# tic12400.net
KiCad netlist of a schematic drawn in EAGLE
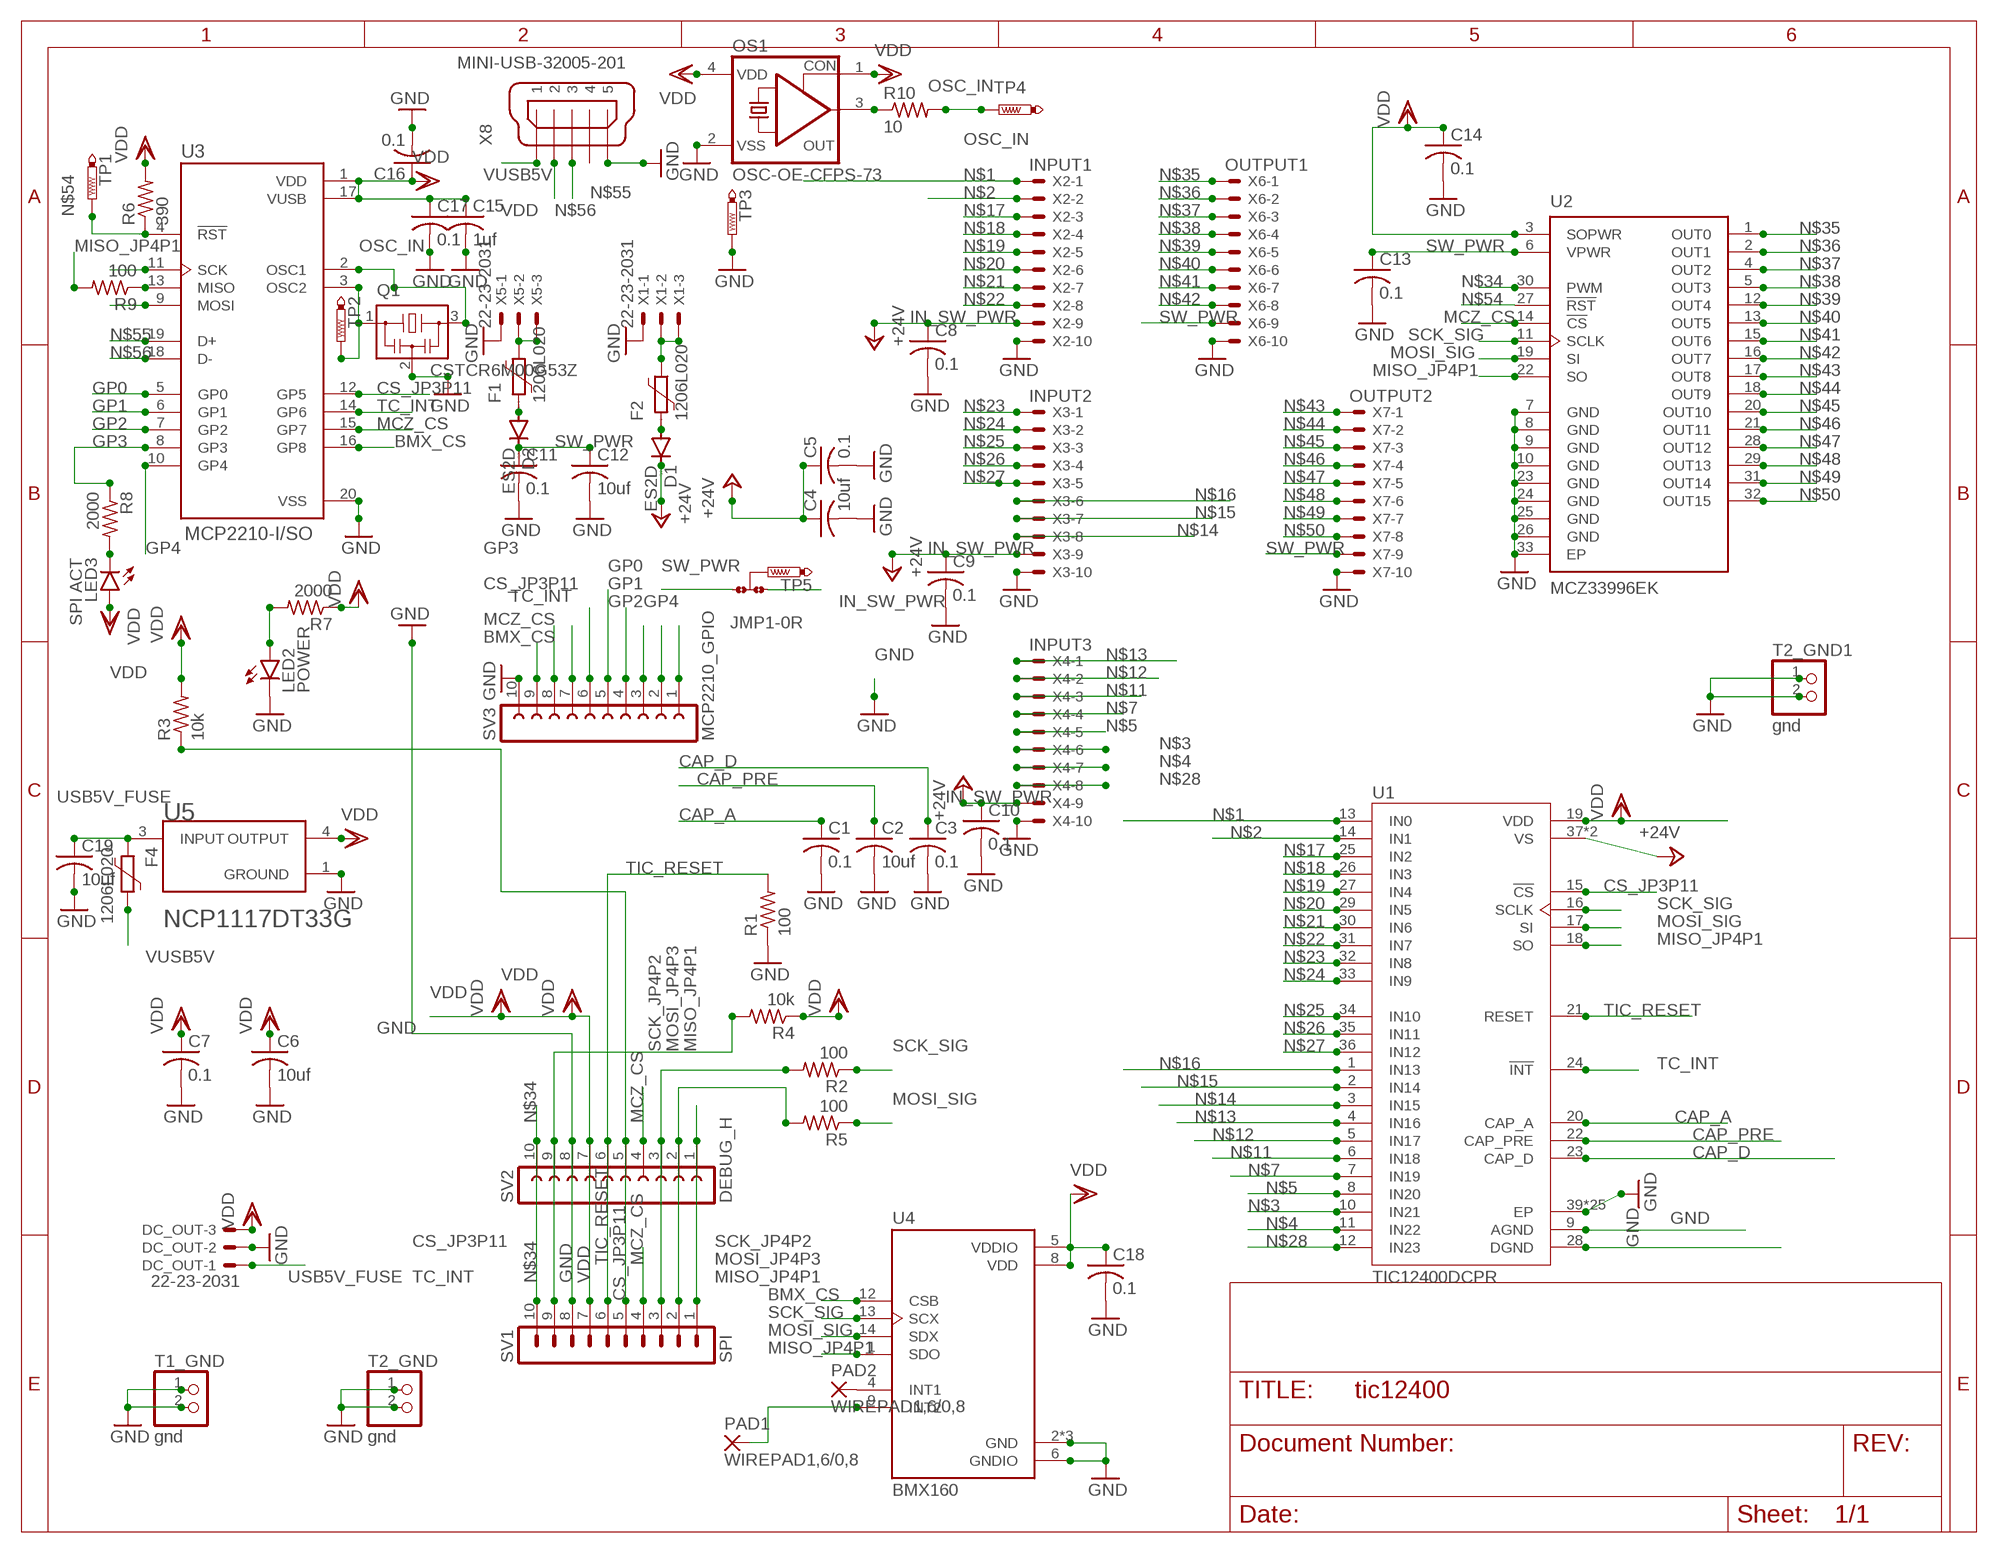
[diagram p0: schematic, sheet 1]

(export (version "E")
  (design (tool "Eeschema 10.0.6"))
  (components
    (comp (ref "C1")
      (value "0.1")
      (footprint "eagle-import:C0805")
      (libsource (lib "eagle-import") (part "C-USC0805"))
    )
    (comp (ref "C2")
      (value "10uf")
      (footprint "eagle-import:C0805")
      (libsource (lib "eagle-import") (part "C-USC0805"))
    )
    (comp (ref "C3")
      (value "0.1")
      (footprint "eagle-import:C0805")
      (libsource (lib "eagle-import") (part "C-USC0805"))
    )
    (comp (ref "C4")
      (value "10uf")
      (footprint "eagle-import:C0805")
      (libsource (lib "eagle-import") (part "C-USC0805"))
    )
    (comp (ref "C5")
      (value "0.1")
      (footprint "eagle-import:C0805")
      (libsource (lib "eagle-import") (part "C-USC0805"))
    )
    (comp (ref "C6")
      (value "10uf")
      (footprint "eagle-import:C0805")
      (libsource (lib "eagle-import") (part "C-USC0805"))
    )
    (comp (ref "C7")
      (value "0.1")
      (footprint "eagle-import:C0805")
      (libsource (lib "eagle-import") (part "C-USC0805"))
    )
    (comp (ref "C8")
      (value "0.1")
      (footprint "eagle-import:C0805")
      (libsource (lib "eagle-import") (part "C-USC0805"))
    )
    (comp (ref "C9")
      (value "0.1")
      (footprint "eagle-import:C0805")
      (libsource (lib "eagle-import") (part "C-USC0805"))
    )
    (comp (ref "C10")
      (value "0.1")
      (footprint "eagle-import:C0805")
      (libsource (lib "eagle-import") (part "C-USC0805"))
    )
    (comp (ref "C11")
      (value "0.1")
      (footprint "eagle-import:C0805")
      (libsource (lib "eagle-import") (part "C-USC0805"))
    )
    (comp (ref "C12")
      (value "10uf")
      (footprint "eagle-import:C0805")
      (libsource (lib "eagle-import") (part "C-USC0805"))
    )
    (comp (ref "C13")
      (value "0.1")
      (footprint "eagle-import:C0805")
      (libsource (lib "eagle-import") (part "C-USC0805"))
    )
    (comp (ref "C14")
      (value "0.1")
      (footprint "eagle-import:C0805")
      (libsource (lib "eagle-import") (part "C-USC0805"))
    )
    (comp (ref "C15")
      (value "1uf")
      (footprint "eagle-import:C0805")
      (libsource (lib "eagle-import") (part "C-USC0805"))
    )
    (comp (ref "C16")
      (value "0.1")
      (footprint "eagle-import:C0805")
      (libsource (lib "eagle-import") (part "C-USC0805"))
    )
    (comp (ref "C17")
      (value "0.1")
      (footprint "eagle-import:C0805")
      (libsource (lib "eagle-import") (part "C-USC0805"))
    )
    (comp (ref "C18")
      (value "0.1")
      (footprint "eagle-import:C0805")
      (libsource (lib "eagle-import") (part "C-USC0805"))
    )
    (comp (ref "C19")
      (value "10uf")
      (footprint "eagle-import:C0805")
      (libsource (lib "eagle-import") (part "C-USC0805"))
    )
    (comp (ref "D1")
      (value "ES2D")
      (footprint "eagle-import:SMB")
      (libsource (lib "eagle-import") (part "ES2D"))
    )
    (comp (ref "D2")
      (value "ES2D")
      (footprint "eagle-import:SMB")
      (libsource (lib "eagle-import") (part "ES2D"))
    )
    (comp (ref "DC_OUT")
      (value "22-23-2031")
      (footprint "eagle-import:22-23-2031")
      (fields (field (name "MF") "MOLEX"))
      (libsource (lib "eagle-import") (part "22-23-2031"))
    )
    (comp (ref "F1")
      (value "1206L020")
      (footprint "eagle-import:1206L")
      (fields (field (name "MF") "Littelfuse"))
      (libsource (lib "eagle-import") (part "?1206L020"))
    )
    (comp (ref "F2")
      (value "1206L020")
      (footprint "eagle-import:1206L")
      (fields (field (name "MF") "Littelfuse"))
      (libsource (lib "eagle-import") (part "?1206L020"))
    )
    (comp (ref "F4")
      (value "1206L020")
      (footprint "eagle-import:1206L")
      (fields (field (name "MF") "Littelfuse"))
      (libsource (lib "eagle-import") (part "?1206L020"))
    )
    (comp (ref "JMP1")
      (value "+24_CONNECT")
      (footprint "eagle-import:A0R-JMP")
      (libsource (lib "eagle-import") (part "0R-JUMPA"))
    )
    (comp (ref "LED2")
      (value "POWER")
      (footprint "eagle-import:CHIP-LED0805")
      (libsource (lib "eagle-import") (part "LEDCHIP-LED0805"))
    )
    (comp (ref "LED3")
      (value "SPI ACT")
      (footprint "eagle-import:CHIP-LED0805")
      (libsource (lib "eagle-import") (part "LEDCHIP-LED0805"))
    )
    (comp (ref "OS1")
      (value "OSC-OE-CFPS-73")
      (footprint "eagle-import:7.2X5.2-4-PAD")
      (libsource (lib "eagle-import") (part "OSC-OE-CFPS-73"))
    )
    (comp (ref "PAD1")
      (value "WIREPAD1,6/0,8")
      (footprint "eagle-import:1,6_0,8")
      (libsource (lib "eagle-import") (part "WIREPAD1,6/0,8"))
    )
    (comp (ref "PAD2")
      (value "WIREPAD1,6/0,8")
      (footprint "eagle-import:1,6_0,8")
      (libsource (lib "eagle-import") (part "WIREPAD1,6/0,8"))
    )
    (comp (ref "Q1")
      (value "CSTCR6M00G53Z")
      (footprint "eagle-import:CSTCR6M")
      (fields (field (name "MPN") "CSTCR6M00G53-R0"))
      (libsource (lib "eagle-import") (part "CSTCR6M00G53Z"))
    )
    (comp (ref "R1")
      (value "100")
      (footprint "eagle-import:R0805")
      (libsource (lib "eagle-import") (part "R-US_R0805"))
    )
    (comp (ref "R2")
      (value "100")
      (footprint "eagle-import:R0805")
      (libsource (lib "eagle-import") (part "R-US_R0805"))
    )
    (comp (ref "R3")
      (value "10k")
      (footprint "eagle-import:R0805")
      (libsource (lib "eagle-import") (part "R-US_R0805"))
    )
    (comp (ref "R4")
      (value "10k")
      (footprint "eagle-import:R0805")
      (libsource (lib "eagle-import") (part "R-US_R0805"))
    )
    (comp (ref "R5")
      (value "100")
      (footprint "eagle-import:R0805")
      (libsource (lib "eagle-import") (part "R-US_R0805"))
    )
    (comp (ref "R6")
      (value "390")
      (footprint "eagle-import:R0805")
      (libsource (lib "eagle-import") (part "R-US_R0805"))
    )
    (comp (ref "R7")
      (value "2000")
      (footprint "eagle-import:R0805")
      (libsource (lib "eagle-import") (part "R-US_R0805"))
    )
    (comp (ref "R8")
      (value "2000")
      (footprint "eagle-import:R0805")
      (libsource (lib "eagle-import") (part "R-US_R0805"))
    )
    (comp (ref "R9")
      (value "100")
      (footprint "eagle-import:R0805")
      (libsource (lib "eagle-import") (part "R-US_R0805"))
    )
    (comp (ref "R10")
      (value "10")
      (footprint "eagle-import:R0805")
      (libsource (lib "eagle-import") (part "R-US_R0805"))
    )
    (comp (ref "SV1")
      (value "SPI")
      (footprint "eagle-import:MA10-1")
      (libsource (lib "eagle-import") (part "MA10-1"))
    )
    (comp (ref "SV2")
      (value "DEBUG_H")
      (footprint "eagle-import:FE10")
      (libsource (lib "eagle-import") (part "FE10-1"))
    )
    (comp (ref "SV3")
      (value "MCP2210_GPIO")
      (footprint "eagle-import:FE10")
      (libsource (lib "eagle-import") (part "FE10-1"))
    )
    (comp (ref "T1_GND")
      (value "gnd")
      (footprint "eagle-import:1X02")
      (libsource (lib "eagle-import") (part "PINHD-1X2"))
    )
    (comp (ref "T2_GND")
      (value "gnd")
      (footprint "eagle-import:1X02")
      (libsource (lib "eagle-import") (part "PINHD-1X2"))
    )
    (comp (ref "T2_GND1")
      (value "gnd")
      (footprint "eagle-import:1X02")
      (libsource (lib "eagle-import") (part "PINHD-1X2"))
    )
    (comp (ref "TP1")
      (value "PTR1B1,27")
      (footprint "eagle-import:B1,27")
      (libsource (lib "eagle-import") (part "PTR1B1,27"))
    )
    (comp (ref "TP2")
      (value "PTR1B1,27")
      (footprint "eagle-import:B1,27")
      (libsource (lib "eagle-import") (part "PTR1B1,27"))
    )
    (comp (ref "TP3")
      (value "PTR1B1,27")
      (footprint "eagle-import:B1,27")
      (libsource (lib "eagle-import") (part "PTR1B1,27"))
    )
    (comp (ref "TP4")
      (value "PTR1B1,27")
      (footprint "eagle-import:B1,27")
      (libsource (lib "eagle-import") (part "PTR1B1,27"))
    )
    (comp (ref "TP5")
      (value "PTR1B1,27")
      (footprint "eagle-import:B1,27")
      (libsource (lib "eagle-import") (part "PTR1B1,27"))
    )
    (comp (ref "U1")
      (value "TIC12400DCPR")
      (footprint "eagle-import:SOP50P640X120-38N")
      (fields (field (name "DIGI-KEY_PART_NUMBER") "296-47492-1-ND") (field (name "MF") "Texas Instruments"))
      (libsource (lib "eagle-import") (part "TIC12400DCPR"))
    )
    (comp (ref "U2")
      (value "MCZ33996EK")
      (footprint "eagle-import:SOP65P1030X265-33N")
      (fields (field (name "MF") "NXP USA"))
      (libsource (lib "eagle-import") (part "MCZ33996EK"))
    )
    (comp (ref "U3")
      (value "MCP2210-I/SO")
      (footprint "eagle-import:SOP65P780X200-20N")
      (fields (field (name "MF") "Microchip Technology"))
      (libsource (lib "eagle-import") (part "MCP2210-I/SO"))
    )
    (comp (ref "U4")
      (value "BMX160")
      (footprint "eagle-import:PQFN50P250X300X100-14N")
      (fields (field (name "MF") "Bosch Sensortec"))
      (libsource (lib "eagle-import") (part "BMX160"))
    )
    (comp (ref "U5")
      (value "ON_SEMICONDUCTOR_NCP1117DT33GON_SEMICONDUCTOR_NCP1117DT33G_0_0")
      (footprint "eagle-import:ON_SEMICONDUCTOR_NCP1117DT33G_0")
      (fields
        (field (name "DIGIKEY_PART_NUMBER") "NCP1117DT33GOS-ND")
        (field (name "MF") "ON Semiconductor")
        (field (name "MOUSER_PART_NUMBER") "863-NCP1117DT33G")
      )
      (libsource (lib "eagle-import") (part "ON_SEMICONDUCTOR_NCP1117DT33GON_SEMICONDUCTOR_NCP1117DT33G_0_0"))
    )
    (comp (ref "X1")
      (value "22-23-2031")
      (footprint "eagle-import:22-23-2031")
      (fields (field (name "MF") "MOLEX"))
      (libsource (lib "eagle-import") (part "22-23-2031"))
    )
    (comp (ref "X2")
      (value "INPUT1")
      (footprint "eagle-import:KK-156-10")
      (fields (field (name "MF") "MOLEX"))
      (libsource (lib "eagle-import") (part "KK-156-10"))
    )
    (comp (ref "X3")
      (value "INPUT2")
      (footprint "eagle-import:KK-156-10")
      (fields (field (name "MF") "MOLEX"))
      (libsource (lib "eagle-import") (part "KK-156-10"))
    )
    (comp (ref "X4")
      (value "INPUT3")
      (footprint "eagle-import:KK-156-10")
      (fields (field (name "MF") "MOLEX"))
      (libsource (lib "eagle-import") (part "KK-156-10"))
    )
    (comp (ref "X5")
      (value "22-23-2031")
      (footprint "eagle-import:22-23-2031")
      (fields (field (name "MF") "MOLEX"))
      (libsource (lib "eagle-import") (part "22-23-2031"))
    )
    (comp (ref "X6")
      (value "OUTPUT1")
      (footprint "eagle-import:KK-156-10")
      (fields (field (name "MF") "MOLEX"))
      (libsource (lib "eagle-import") (part "KK-156-10"))
    )
    (comp (ref "X7")
      (value "OUTPUT2")
      (footprint "eagle-import:KK-156-10")
      (fields (field (name "MF") "MOLEX"))
      (libsource (lib "eagle-import") (part "KK-156-10"))
    )
    (comp (ref "X8")
      (value "MINI-USB-32005-201")
      (footprint "eagle-import:32005-201")
      (libsource (lib "eagle-import") (part "MINI-USB-32005-201"))
    )
  )
  (nets
    (net (code "1") (name "+24V") (class "Default")
      (node (ref "C10") (pin "1") (pinfunction "1_1") (pintype "passive"))
      (node (ref "C4") (pin "1") (pinfunction "1_1") (pintype "passive"))
      (node (ref "C5") (pin "1") (pinfunction "1_1") (pintype "passive"))
      (node (ref "C8") (pin "1") (pinfunction "1_1") (pintype "passive"))
      (node (ref "C9") (pin "1") (pinfunction "1_1") (pintype "passive"))
      (node (ref "D1") (pin "C") (pinfunction "C_C") (pintype "passive"))
      (node (ref "JMP1") (pin "3") (pinfunction "3_3") (pintype "passive"))
      (node (ref "U1") (pin "37") (pinfunction "VS_37") (pintype "power_in"))
      (node (ref "U1") (pin "38") (pinfunction "VS_38") (pintype "power_in"))
      (node (ref "X2") (pin "9") (pinfunction "S_9") (pintype "passive"))
      (node (ref "X3") (pin "9") (pinfunction "S_9") (pintype "passive"))
      (node (ref "X4") (pin "9") (pinfunction "S_9") (pintype "passive"))
    )
    (net (code "2") (name "/BMX_CS") (class "Default")
      (node (ref "SV3") (pin "9") (pinfunction "9_9") (pintype "passive"))
      (node (ref "U3") (pin "16") (pinfunction "GP8_16") (pintype "bidirectional"))
      (node (ref "U4") (pin "12") (pinfunction "CSB_12") (pintype "input"))
    )
    (net (code "3") (name "/CAP_A") (class "Default")
      (node (ref "C1") (pin "1") (pinfunction "1_1") (pintype "passive"))
      (node (ref "U1") (pin "20") (pinfunction "CAP_A_20") (pintype "passive"))
    )
    (net (code "4") (name "/CAP_D") (class "Default")
      (node (ref "C3") (pin "1") (pinfunction "1_1") (pintype "passive"))
      (node (ref "U1") (pin "23") (pinfunction "CAP_D_23") (pintype "passive"))
    )
    (net (code "5") (name "/CAP_PRE") (class "Default")
      (node (ref "C2") (pin "1") (pinfunction "1_1") (pintype "passive"))
      (node (ref "U1") (pin "22") (pinfunction "CAP_PRE_22") (pintype "passive"))
    )
    (net (code "6") (name "/CS_JP3P11") (class "Default")
      (node (ref "R3") (pin "1") (pinfunction "1_1") (pintype "passive"))
      (node (ref "SV1") (pin "5") (pinfunction "5_5") (pintype "passive"))
      (node (ref "SV2") (pin "5") (pinfunction "5_5") (pintype "passive"))
      (node (ref "SV3") (pin "6") (pinfunction "6_6") (pintype "passive"))
      (node (ref "U1") (pin "15") (pinfunction "~{CS}_15") (pintype "input"))
      (node (ref "U3") (pin "12") (pinfunction "GP5_12") (pintype "bidirectional"))
    )
    (net (code "7") (name "/GP0") (class "Default")
      (node (ref "SV3") (pin "1") (pinfunction "1_1") (pintype "passive"))
      (node (ref "U3") (pin "5") (pinfunction "GP0_5") (pintype "bidirectional"))
    )
    (net (code "8") (name "/GP1") (class "Default")
      (node (ref "SV3") (pin "2") (pinfunction "2_2") (pintype "passive"))
      (node (ref "U3") (pin "6") (pinfunction "GP1_6") (pintype "bidirectional"))
    )
    (net (code "9") (name "/GP2") (class "Default")
      (node (ref "SV3") (pin "3") (pinfunction "3_3") (pintype "passive"))
      (node (ref "U3") (pin "7") (pinfunction "GP2_7") (pintype "bidirectional"))
    )
    (net (code "10") (name "/GP3") (class "Default")
      (node (ref "R8") (pin "1") (pinfunction "1_1") (pintype "passive"))
      (node (ref "SV3") (pin "4") (pinfunction "4_4") (pintype "passive"))
      (node (ref "U3") (pin "8") (pinfunction "GP3_8") (pintype "bidirectional"))
    )
    (net (code "11") (name "/GP4") (class "Default")
      (node (ref "SV3") (pin "5") (pinfunction "5_5") (pintype "passive"))
      (node (ref "U3") (pin "10") (pinfunction "GP4_10") (pintype "bidirectional"))
    )
    (net (code "12") (name "/MCZ_CS") (class "Default")
      (node (ref "SV1") (pin "4") (pinfunction "4_4") (pintype "passive"))
      (node (ref "SV2") (pin "4") (pinfunction "4_4") (pintype "passive"))
      (node (ref "SV3") (pin "8") (pinfunction "8_8") (pintype "passive"))
      (node (ref "U2") (pin "14") (pinfunction "~{CS}_14") (pintype "input"))
      (node (ref "U3") (pin "15") (pinfunction "GP7_15") (pintype "bidirectional"))
    )
    (net (code "13") (name "/MISO_JP4P1") (class "Default")
      (node (ref "R9") (pin "2") (pinfunction "2_2") (pintype "passive"))
      (node (ref "SV1") (pin "1") (pinfunction "1_1") (pintype "passive"))
      (node (ref "SV2") (pin "1") (pinfunction "1_1") (pintype "passive"))
      (node (ref "U1") (pin "18") (pinfunction "SO_18") (pintype "output"))
      (node (ref "U2") (pin "22") (pinfunction "SO_22") (pintype "output"))
      (node (ref "U4") (pin "1") (pinfunction "SDO_1") (pintype "bidirectional"))
    )
    (net (code "14") (name "/MOSI_JP4P3") (class "Default")
      (node (ref "R5") (pin "2") (pinfunction "2_2") (pintype "passive"))
      (node (ref "SV1") (pin "2") (pinfunction "2_2") (pintype "passive"))
      (node (ref "SV2") (pin "2") (pinfunction "2_2") (pintype "passive"))
    )
    (net (code "15") (name "/MOSI_SIG") (class "Default")
      (node (ref "R5") (pin "1") (pinfunction "1_1") (pintype "passive"))
      (node (ref "U1") (pin "17") (pinfunction "SI_17") (pintype "input"))
      (node (ref "U2") (pin "19") (pinfunction "SI_19") (pintype "input"))
      (node (ref "U3") (pin "9") (pinfunction "MOSI_9") (pintype "output"))
      (node (ref "U4") (pin "14") (pinfunction "SDX_14") (pintype "bidirectional"))
    )
    (net (code "16") (name "/N$1") (class "Default")
      (node (ref "U1") (pin "13") (pinfunction "IN0_13") (pintype "bidirectional"))
      (node (ref "X2") (pin "1") (pinfunction "S_1") (pintype "passive"))
    )
    (net (code "17") (name "/N$2") (class "Default")
      (node (ref "U1") (pin "14") (pinfunction "IN1_14") (pintype "bidirectional"))
      (node (ref "X2") (pin "2") (pinfunction "S_2") (pintype "passive"))
    )
    (net (code "18") (name "/N$3") (class "Default")
      (node (ref "U1") (pin "10") (pinfunction "IN21_10") (pintype "bidirectional"))
      (node (ref "X4") (pin "6") (pinfunction "S_6") (pintype "passive"))
    )
    (net (code "19") (name "/N$4") (class "Default")
      (node (ref "U1") (pin "11") (pinfunction "IN22_11") (pintype "bidirectional"))
      (node (ref "X4") (pin "7") (pinfunction "S_7") (pintype "passive"))
    )
    (net (code "20") (name "/N$5") (class "Default")
      (node (ref "U1") (pin "8") (pinfunction "IN20_8") (pintype "bidirectional"))
      (node (ref "X4") (pin "5") (pinfunction "S_5") (pintype "passive"))
    )
    (net (code "21") (name "/N$7") (class "Default")
      (node (ref "U1") (pin "7") (pinfunction "IN19_7") (pintype "bidirectional"))
      (node (ref "X4") (pin "4") (pinfunction "S_4") (pintype "passive"))
    )
    (net (code "22") (name "/N$11") (class "Default")
      (node (ref "U1") (pin "6") (pinfunction "IN18_6") (pintype "bidirectional"))
      (node (ref "X4") (pin "3") (pinfunction "S_3") (pintype "passive"))
    )
    (net (code "23") (name "/N$12") (class "Default")
      (node (ref "U1") (pin "5") (pinfunction "IN17_5") (pintype "bidirectional"))
      (node (ref "X4") (pin "2") (pinfunction "S_2") (pintype "passive"))
    )
    (net (code "24") (name "/N$13") (class "Default")
      (node (ref "U1") (pin "4") (pinfunction "IN16_4") (pintype "bidirectional"))
      (node (ref "X4") (pin "1") (pinfunction "S_1") (pintype "passive"))
    )
    (net (code "25") (name "/N$14") (class "Default")
      (node (ref "U1") (pin "3") (pinfunction "IN15_3") (pintype "bidirectional"))
      (node (ref "X3") (pin "8") (pinfunction "S_8") (pintype "passive"))
    )
    (net (code "26") (name "/N$15") (class "Default")
      (node (ref "U1") (pin "2") (pinfunction "IN14_2") (pintype "bidirectional"))
      (node (ref "X3") (pin "7") (pinfunction "S_7") (pintype "passive"))
    )
    (net (code "27") (name "/N$16") (class "Default")
      (node (ref "U1") (pin "1") (pinfunction "IN13_1") (pintype "bidirectional"))
      (node (ref "X3") (pin "6") (pinfunction "S_6") (pintype "passive"))
    )
    (net (code "28") (name "/N$17") (class "Default")
      (node (ref "U1") (pin "25") (pinfunction "IN2_25") (pintype "bidirectional"))
      (node (ref "X2") (pin "3") (pinfunction "S_3") (pintype "passive"))
    )
    (net (code "29") (name "/N$18") (class "Default")
      (node (ref "U1") (pin "26") (pinfunction "IN3_26") (pintype "bidirectional"))
      (node (ref "X2") (pin "4") (pinfunction "S_4") (pintype "passive"))
    )
    (net (code "30") (name "/N$19") (class "Default")
      (node (ref "U1") (pin "27") (pinfunction "IN4_27") (pintype "bidirectional"))
      (node (ref "X2") (pin "5") (pinfunction "S_5") (pintype "passive"))
    )
    (net (code "31") (name "/N$20") (class "Default")
      (node (ref "U1") (pin "29") (pinfunction "IN5_29") (pintype "bidirectional"))
      (node (ref "X2") (pin "6") (pinfunction "S_6") (pintype "passive"))
    )
    (net (code "32") (name "/N$21") (class "Default")
      (node (ref "U1") (pin "30") (pinfunction "IN6_30") (pintype "bidirectional"))
      (node (ref "X2") (pin "7") (pinfunction "S_7") (pintype "passive"))
    )
    (net (code "33") (name "/N$22") (class "Default")
      (node (ref "U1") (pin "31") (pinfunction "IN7_31") (pintype "bidirectional"))
      (node (ref "X2") (pin "8") (pinfunction "S_8") (pintype "passive"))
    )
    (net (code "34") (name "/N$23") (class "Default")
      (node (ref "U1") (pin "32") (pinfunction "IN8_32") (pintype "bidirectional"))
      (node (ref "X3") (pin "1") (pinfunction "S_1") (pintype "passive"))
    )
    (net (code "35") (name "/N$24") (class "Default")
      (node (ref "U1") (pin "33") (pinfunction "IN9_33") (pintype "bidirectional"))
      (node (ref "X3") (pin "2") (pinfunction "S_2") (pintype "passive"))
    )
    (net (code "36") (name "/N$25") (class "Default")
      (node (ref "U1") (pin "34") (pinfunction "IN10_34") (pintype "bidirectional"))
      (node (ref "X3") (pin "3") (pinfunction "S_3") (pintype "passive"))
    )
    (net (code "37") (name "/N$26") (class "Default")
      (node (ref "U1") (pin "35") (pinfunction "IN11_35") (pintype "bidirectional"))
      (node (ref "X3") (pin "4") (pinfunction "S_4") (pintype "passive"))
    )
    (net (code "38") (name "/N$27") (class "Default")
      (node (ref "U1") (pin "36") (pinfunction "IN12_36") (pintype "bidirectional"))
      (node (ref "X3") (pin "5") (pinfunction "S_5") (pintype "passive"))
    )
    (net (code "39") (name "/N$28") (class "Default")
      (node (ref "U1") (pin "12") (pinfunction "IN23_12") (pintype "bidirectional"))
      (node (ref "X4") (pin "8") (pinfunction "S_8") (pintype "passive"))
    )
    (net (code "40") (name "/N$34") (class "Default")
      (node (ref "SV1") (pin "10") (pinfunction "10_10") (pintype "passive"))
      (node (ref "SV2") (pin "10") (pinfunction "10_10") (pintype "passive"))
      (node (ref "U2") (pin "30") (pinfunction "PWM_30") (pintype "input"))
    )
    (net (code "41") (name "/N$35") (class "Default")
      (node (ref "U2") (pin "1") (pinfunction "OUT0_1") (pintype "output"))
      (node (ref "X6") (pin "1") (pinfunction "S_1") (pintype "passive"))
    )
    (net (code "42") (name "/N$36") (class "Default")
      (node (ref "U2") (pin "2") (pinfunction "OUT1_2") (pintype "output"))
      (node (ref "X6") (pin "2") (pinfunction "S_2") (pintype "passive"))
    )
    (net (code "43") (name "/N$37") (class "Default")
      (node (ref "U2") (pin "4") (pinfunction "OUT2_4") (pintype "output"))
      (node (ref "X6") (pin "3") (pinfunction "S_3") (pintype "passive"))
    )
    (net (code "44") (name "/N$38") (class "Default")
      (node (ref "U2") (pin "5") (pinfunction "OUT3_5") (pintype "output"))
      (node (ref "X6") (pin "4") (pinfunction "S_4") (pintype "passive"))
    )
    (net (code "45") (name "/N$39") (class "Default")
      (node (ref "U2") (pin "12") (pinfunction "OUT4_12") (pintype "output"))
      (node (ref "X6") (pin "5") (pinfunction "S_5") (pintype "passive"))
    )
    (net (code "46") (name "/N$40") (class "Default")
      (node (ref "U2") (pin "13") (pinfunction "OUT5_13") (pintype "output"))
      (node (ref "X6") (pin "6") (pinfunction "S_6") (pintype "passive"))
    )
    (net (code "47") (name "/N$41") (class "Default")
      (node (ref "U2") (pin "15") (pinfunction "OUT6_15") (pintype "output"))
      (node (ref "X6") (pin "7") (pinfunction "S_7") (pintype "passive"))
    )
    (net (code "48") (name "/N$42") (class "Default")
      (node (ref "U2") (pin "16") (pinfunction "OUT7_16") (pintype "output"))
      (node (ref "X6") (pin "8") (pinfunction "S_8") (pintype "passive"))
    )
    (net (code "49") (name "/N$43") (class "Default")
      (node (ref "U2") (pin "17") (pinfunction "OUT8_17") (pintype "output"))
      (node (ref "X7") (pin "1") (pinfunction "S_1") (pintype "passive"))
    )
    (net (code "50") (name "/N$44") (class "Default")
      (node (ref "U2") (pin "18") (pinfunction "OUT9_18") (pintype "output"))
      (node (ref "X7") (pin "2") (pinfunction "S_2") (pintype "passive"))
    )
    (net (code "51") (name "/N$45") (class "Default")
      (node (ref "U2") (pin "20") (pinfunction "OUT10_20") (pintype "output"))
      (node (ref "X7") (pin "3") (pinfunction "S_3") (pintype "passive"))
    )
    (net (code "52") (name "/N$46") (class "Default")
      (node (ref "U2") (pin "21") (pinfunction "OUT11_21") (pintype "output"))
      (node (ref "X7") (pin "4") (pinfunction "S_4") (pintype "passive"))
    )
    (net (code "53") (name "/N$47") (class "Default")
      (node (ref "U2") (pin "28") (pinfunction "OUT12_28") (pintype "output"))
      (node (ref "X7") (pin "5") (pinfunction "S_5") (pintype "passive"))
    )
    (net (code "54") (name "/N$48") (class "Default")
      (node (ref "U2") (pin "29") (pinfunction "OUT13_29") (pintype "output"))
      (node (ref "X7") (pin "6") (pinfunction "S_6") (pintype "passive"))
    )
    (net (code "55") (name "/N$49") (class "Default")
      (node (ref "U2") (pin "31") (pinfunction "OUT14_31") (pintype "output"))
      (node (ref "X7") (pin "7") (pinfunction "S_7") (pintype "passive"))
    )
    (net (code "56") (name "/N$50") (class "Default")
      (node (ref "U2") (pin "32") (pinfunction "OUT15_32") (pintype "output"))
      (node (ref "X7") (pin "8") (pinfunction "S_8") (pintype "passive"))
    )
    (net (code "57") (name "/N$54") (class "Default")
      (node (ref "R6") (pin "1") (pinfunction "1_1") (pintype "passive"))
      (node (ref "TP1") (pin "TP") (pinfunction "TP_TP") (pintype "input"))
      (node (ref "U2") (pin "27") (pinfunction "~{RST}_27") (pintype "input"))
      (node (ref "U3") (pin "4") (pinfunction "~{RST}_4") (pintype "input"))
    )
    (net (code "58") (name "/N$55") (class "Default")
      (node (ref "U3") (pin "19") (pinfunction "D+_19") (pintype "bidirectional"))
      (node (ref "X8") (pin "3") (pinfunction "3_3") (pintype "passive"))
    )
    (net (code "59") (name "/N$56") (class "Default")
      (node (ref "U3") (pin "18") (pinfunction "D-_18") (pintype "bidirectional"))
      (node (ref "X8") (pin "2") (pinfunction "2_2") (pintype "passive"))
    )
    (net (code "60") (name "/OSC_IN") (class "Default")
      (node (ref "Q1") (pin "3") (pinfunction "3_3") (pintype "passive"))
      (node (ref "R10") (pin "2") (pinfunction "2_2") (pintype "passive"))
      (node (ref "TP4") (pin "TP") (pinfunction "TP_TP") (pintype "input"))
      (node (ref "U3") (pin "2") (pinfunction "OSC1_2") (pintype "input"))
    )
    (net (code "61") (name "/SCK_JP4P2") (class "Default")
      (node (ref "R2") (pin "2") (pinfunction "2_2") (pintype "passive"))
      (node (ref "SV1") (pin "3") (pinfunction "3_3") (pintype "passive"))
      (node (ref "SV2") (pin "3") (pinfunction "3_3") (pintype "passive"))
    )
    (net (code "62") (name "/SCK_SIG") (class "Default")
      (node (ref "R2") (pin "1") (pinfunction "1_1") (pintype "passive"))
      (node (ref "U1") (pin "16") (pinfunction "SCLK_16") (pintype "input"))
      (node (ref "U2") (pin "11") (pinfunction "SCLK_11") (pintype "input"))
      (node (ref "U3") (pin "11") (pinfunction "SCK_11") (pintype "output"))
      (node (ref "U4") (pin "13") (pinfunction "SCX_13") (pintype "input"))
    )
    (net (code "63") (name "/SW_PWR") (class "Default")
      (node (ref "C11") (pin "1") (pinfunction "1_1") (pintype "passive"))
      (node (ref "C12") (pin "1") (pinfunction "1_1") (pintype "passive"))
      (node (ref "C13") (pin "1") (pinfunction "1_1") (pintype "passive"))
      (node (ref "D2") (pin "C") (pinfunction "C_C") (pintype "passive"))
      (node (ref "JMP1") (pin "1") (pinfunction "1_1") (pintype "passive"))
      (node (ref "U2") (pin "6") (pinfunction "VPWR_6") (pintype "power_in"))
      (node (ref "X6") (pin "9") (pinfunction "S_9") (pintype "passive"))
      (node (ref "X7") (pin "9") (pinfunction "S_9") (pintype "passive"))
    )
    (net (code "64") (name "/TC_INT") (class "Default")
      (node (ref "R4") (pin "2") (pinfunction "2_2") (pintype "passive"))
      (node (ref "SV1") (pin "9") (pinfunction "9_9") (pintype "passive"))
      (node (ref "SV2") (pin "9") (pinfunction "9_9") (pintype "passive"))
      (node (ref "SV3") (pin "7") (pinfunction "7_7") (pintype "passive"))
      (node (ref "U1") (pin "24") (pinfunction "~{INT}_24") (pintype "output"))
      (node (ref "U3") (pin "14") (pinfunction "GP6_14") (pintype "bidirectional"))
    )
    (net (code "65") (name "/TIC_RESET") (class "Default")
      (node (ref "R1") (pin "2") (pinfunction "2_2") (pintype "passive"))
      (node (ref "SV1") (pin "6") (pinfunction "6_6") (pintype "passive"))
      (node (ref "SV2") (pin "6") (pinfunction "6_6") (pintype "passive"))
      (node (ref "U1") (pin "21") (pinfunction "RESET_21") (pintype "input"))
    )
    (net (code "66") (name "/USB5V_FUSE") (class "Default")
      (node (ref "C19") (pin "1") (pinfunction "1_1") (pintype "passive"))
      (node (ref "DC_OUT") (pin "1") (pinfunction "S_1") (pintype "passive"))
      (node (ref "F4") (pin "2") (pinfunction "2_2") (pintype "passive"))
      (node (ref "U5") (pin "3") (pinfunction "INPUT_3") (pintype "input"))
    )
    (net (code "67") (name "/VUSB5V") (class "Default")
      (node (ref "F4") (pin "1") (pinfunction "1_1") (pintype "passive"))
      (node (ref "X8") (pin "1") (pinfunction "1_1") (pintype "passive"))
    )
    (net (code "68") (name "GND") (class "Default")
      (node (ref "C1") (pin "2") (pinfunction "2_2") (pintype "passive"))
      (node (ref "C10") (pin "2") (pinfunction "2_2") (pintype "passive"))
      (node (ref "C11") (pin "2") (pinfunction "2_2") (pintype "passive"))
      (node (ref "C12") (pin "2") (pinfunction "2_2") (pintype "passive"))
      (node (ref "C13") (pin "2") (pinfunction "2_2") (pintype "passive"))
      (node (ref "C14") (pin "2") (pinfunction "2_2") (pintype "passive"))
      (node (ref "C15") (pin "2") (pinfunction "2_2") (pintype "passive"))
      (node (ref "C16") (pin "2") (pinfunction "2_2") (pintype "passive"))
      (node (ref "C17") (pin "2") (pinfunction "2_2") (pintype "passive"))
      (node (ref "C18") (pin "2") (pinfunction "2_2") (pintype "passive"))
      (node (ref "C19") (pin "2") (pinfunction "2_2") (pintype "passive"))
      (node (ref "C2") (pin "2") (pinfunction "2_2") (pintype "passive"))
      (node (ref "C3") (pin "2") (pinfunction "2_2") (pintype "passive"))
      (node (ref "C4") (pin "2") (pinfunction "2_2") (pintype "passive"))
      (node (ref "C5") (pin "2") (pinfunction "2_2") (pintype "passive"))
      (node (ref "C6") (pin "2") (pinfunction "2_2") (pintype "passive"))
      (node (ref "C7") (pin "2") (pinfunction "2_2") (pintype "passive"))
      (node (ref "C8") (pin "2") (pinfunction "2_2") (pintype "passive"))
      (node (ref "C9") (pin "2") (pinfunction "2_2") (pintype "passive"))
      (node (ref "DC_OUT") (pin "2") (pinfunction "S_2") (pintype "passive"))
      (node (ref "LED2") (pin "C") (pinfunction "C_C") (pintype "passive"))
      (node (ref "OS1") (pin "2") (pinfunction "VSS_2") (pintype "power_in"))
      (node (ref "Q1") (pin "2") (pinfunction "2_2") (pintype "passive"))
      (node (ref "R1") (pin "1") (pinfunction "1_1") (pintype "passive"))
      (node (ref "SV1") (pin "8") (pinfunction "8_8") (pintype "passive"))
      (node (ref "SV2") (pin "8") (pinfunction "8_8") (pintype "passive"))
      (node (ref "SV3") (pin "10") (pinfunction "10_10") (pintype "passive"))
      (node (ref "T1_GND") (pin "1") (pinfunction "1_1") (pintype "passive"))
      (node (ref "T1_GND") (pin "2") (pinfunction "2_2") (pintype "passive"))
      (node (ref "T2_GND") (pin "1") (pinfunction "1_1") (pintype "passive"))
      (node (ref "T2_GND") (pin "2") (pinfunction "2_2") (pintype "passive"))
      (node (ref "T2_GND1") (pin "1") (pinfunction "1_1") (pintype "passive"))
      (node (ref "T2_GND1") (pin "2") (pinfunction "2_2") (pintype "passive"))
      (node (ref "TP3") (pin "TP") (pinfunction "TP_TP") (pintype "input"))
      (node (ref "U1") (pin "28") (pinfunction "DGND_28") (pintype "power_in"))
      (node (ref "U1") (pin "39") (pinfunction "EP_39") (pintype "power_in"))
      (node (ref "U1") (pin "40") (pinfunction "EP_40") (pintype "power_in"))
      (node (ref "U1") (pin "41") (pinfunction "EP_41") (pintype "power_in"))
      (node (ref "U1") (pin "42") (pinfunction "EP_42") (pintype "power_in"))
      (node (ref "U1") (pin "43") (pinfunction "EP_43") (pintype "power_in"))
      (node (ref "U1") (pin "44") (pinfunction "EP_44") (pintype "power_in"))
      (node (ref "U1") (pin "45") (pinfunction "EP_45") (pintype "power_in"))
      (node (ref "U1") (pin "46") (pinfunction "EP_46") (pintype "power_in"))
      (node (ref "U1") (pin "47") (pinfunction "EP_47") (pintype "power_in"))
      (node (ref "U1") (pin "48") (pinfunction "EP_48") (pintype "power_in"))
      (node (ref "U1") (pin "49") (pinfunction "EP_49") (pintype "power_in"))
      (node (ref "U1") (pin "50") (pinfunction "EP_50") (pintype "power_in"))
      (node (ref "U1") (pin "51") (pinfunction "EP_51") (pintype "power_in"))
      (node (ref "U1") (pin "52") (pinfunction "EP_52") (pintype "power_in"))
      (node (ref "U1") (pin "53") (pinfunction "EP_53") (pintype "power_in"))
      (node (ref "U1") (pin "54") (pinfunction "EP_54") (pintype "power_in"))
      (node (ref "U1") (pin "55") (pinfunction "EP_55") (pintype "power_in"))
      (node (ref "U1") (pin "56") (pinfunction "EP_56") (pintype "power_in"))
      (node (ref "U1") (pin "57") (pinfunction "EP_57") (pintype "power_in"))
      (node (ref "U1") (pin "58") (pinfunction "EP_58") (pintype "power_in"))
      (node (ref "U1") (pin "59") (pinfunction "EP_59") (pintype "power_in"))
      (node (ref "U1") (pin "60") (pinfunction "EP_60") (pintype "power_in"))
      (node (ref "U1") (pin "61") (pinfunction "EP_61") (pintype "power_in"))
      (node (ref "U1") (pin "62") (pinfunction "EP_62") (pintype "power_in"))
      (node (ref "U1") (pin "63") (pinfunction "EP_63") (pintype "power_in"))
      (node (ref "U1") (pin "9") (pinfunction "AGND_9") (pintype "power_in"))
      (node (ref "U2") (pin "10") (pinfunction "GND_10") (pintype "power_in"))
      (node (ref "U2") (pin "23") (pinfunction "GND_23") (pintype "power_in"))
      (node (ref "U2") (pin "24") (pinfunction "GND_24") (pintype "power_in"))
      (node (ref "U2") (pin "25") (pinfunction "GND_25") (pintype "power_in"))
      (node (ref "U2") (pin "26") (pinfunction "GND_26") (pintype "power_in"))
      (node (ref "U2") (pin "33") (pinfunction "EP_33") (pintype "power_in"))
      (node (ref "U2") (pin "7") (pinfunction "GND_7") (pintype "power_in"))
      (node (ref "U2") (pin "8") (pinfunction "GND_8") (pintype "power_in"))
      (node (ref "U2") (pin "9") (pinfunction "GND_9") (pintype "power_in"))
      (node (ref "U3") (pin "20") (pinfunction "VSS_20") (pintype "power_in"))
      (node (ref "U4") (pin "2") (pinfunction "GND_2") (pintype "power_in"))
      (node (ref "U4") (pin "3") (pinfunction "GND_3") (pintype "power_in"))
      (node (ref "U4") (pin "6") (pinfunction "GNDIO_6") (pintype "power_in"))
      (node (ref "U4") (pin "7") (pinfunction "GND_7") (pintype "power_in"))
      (node (ref "U5") (pin "1") (pinfunction "GROUND_1") (pintype "power_in"))
      (node (ref "X1") (pin "1") (pinfunction "S_1") (pintype "passive"))
      (node (ref "X2") (pin "10") (pinfunction "S_10") (pintype "passive"))
      (node (ref "X3") (pin "10") (pinfunction "S_10") (pintype "passive"))
      (node (ref "X4") (pin "10") (pinfunction "S_10") (pintype "passive"))
      (node (ref "X5") (pin "1") (pinfunction "S_1") (pintype "passive"))
      (node (ref "X6") (pin "10") (pinfunction "S_10") (pintype "passive"))
      (node (ref "X7") (pin "10") (pinfunction "S_10") (pintype "passive"))
      (node (ref "X8") (pin "5") (pinfunction "5_5") (pintype "passive"))
    )
    (net (code "69") (name "Net-(D1-PadA)") (class "Default")
      (node (ref "D1") (pin "A") (pinfunction "A_A") (pintype "passive"))
      (node (ref "F2") (pin "2") (pinfunction "2_2") (pintype "passive"))
    )
    (net (code "70") (name "Net-(D2-PadA)") (class "Default")
      (node (ref "D2") (pin "A") (pinfunction "A_A") (pintype "passive"))
      (node (ref "F1") (pin "2") (pinfunction "2_2") (pintype "passive"))
    )
    (net (code "71") (name "Net-(JMP1-Pad2)") (class "Default")
      (node (ref "JMP1") (pin "2") (pinfunction "2_2") (pintype "passive"))
      (node (ref "TP5") (pin "TP") (pinfunction "TP_TP") (pintype "input"))
    )
    (net (code "72") (name "Net-(LED2-PadA)") (class "Default")
      (node (ref "LED2") (pin "A") (pinfunction "A_A") (pintype "passive"))
      (node (ref "R7") (pin "2") (pinfunction "2_2") (pintype "passive"))
    )
    (net (code "73") (name "Net-(LED3-PadC)") (class "Default")
      (node (ref "LED3") (pin "C") (pinfunction "C_C") (pintype "passive"))
      (node (ref "R8") (pin "2") (pinfunction "2_2") (pintype "passive"))
    )
    (net (code "74") (name "Net-(OS1-OUT)") (class "Default")
      (node (ref "OS1") (pin "3") (pinfunction "OUT_3") (pintype "output"))
      (node (ref "R10") (pin "1") (pinfunction "1_1") (pintype "passive"))
    )
    (net (code "75") (name "Net-(PAD1-P)") (class "Default")
      (node (ref "PAD1") (pin "1") (pinfunction "P_1") (pintype "passive"))
      (node (ref "U4") (pin "9") (pinfunction "INT2_9") (pintype "bidirectional"))
    )
    (net (code "76") (name "Net-(PAD2-P)") (class "Default")
      (node (ref "PAD2") (pin "1") (pinfunction "P_1") (pintype "passive"))
      (node (ref "U4") (pin "4") (pinfunction "INT1_4") (pintype "bidirectional"))
    )
    (net (code "77") (name "Net-(U3-MISO)") (class "Default")
      (node (ref "R9") (pin "1") (pinfunction "1_1") (pintype "passive"))
      (node (ref "U3") (pin "13") (pinfunction "MISO_13") (pintype "input"))
    )
    (net (code "78") (name "Net-(U3-OSC2)") (class "Default")
      (node (ref "Q1") (pin "1") (pinfunction "1_1") (pintype "passive"))
      (node (ref "TP2") (pin "TP") (pinfunction "TP_TP") (pintype "input"))
      (node (ref "U3") (pin "3") (pinfunction "OSC2_3") (pintype "output"))
    )
    (net (code "79") (name "Net-(X1B-S)") (class "Default")
      (node (ref "F2") (pin "1") (pinfunction "1_1") (pintype "passive"))
      (node (ref "X1") (pin "2") (pinfunction "S_2") (pintype "passive"))
      (node (ref "X1") (pin "3") (pinfunction "S_3") (pintype "passive"))
    )
    (net (code "80") (name "Net-(X5B-S)") (class "Default")
      (node (ref "F1") (pin "1") (pinfunction "1_1") (pintype "passive"))
      (node (ref "X5") (pin "2") (pinfunction "S_2") (pintype "passive"))
      (node (ref "X5") (pin "3") (pinfunction "S_3") (pintype "passive"))
    )
    (net (code "81") (name "VDD") (class "Default")
      (node (ref "C14") (pin "1") (pinfunction "1_1") (pintype "passive"))
      (node (ref "C15") (pin "1") (pinfunction "1_1") (pintype "passive"))
      (node (ref "C16") (pin "1") (pinfunction "1_1") (pintype "passive"))
      (node (ref "C17") (pin "1") (pinfunction "1_1") (pintype "passive"))
      (node (ref "C18") (pin "1") (pinfunction "1_1") (pintype "passive"))
      (node (ref "C6") (pin "1") (pinfunction "1_1") (pintype "passive"))
      (node (ref "C7") (pin "1") (pinfunction "1_1") (pintype "passive"))
      (node (ref "DC_OUT") (pin "3") (pinfunction "S_3") (pintype "passive"))
      (node (ref "LED3") (pin "A") (pinfunction "A_A") (pintype "passive"))
      (node (ref "OS1") (pin "1") (pinfunction "CON_1") (pintype "input"))
      (node (ref "OS1") (pin "4") (pinfunction "VDD_4") (pintype "power_in"))
      (node (ref "R3") (pin "2") (pinfunction "2_2") (pintype "passive"))
      (node (ref "R4") (pin "1") (pinfunction "1_1") (pintype "passive"))
      (node (ref "R6") (pin "2") (pinfunction "2_2") (pintype "passive"))
      (node (ref "R7") (pin "1") (pinfunction "1_1") (pintype "passive"))
      (node (ref "SV1") (pin "7") (pinfunction "7_7") (pintype "passive"))
      (node (ref "SV2") (pin "7") (pinfunction "7_7") (pintype "passive"))
      (node (ref "U1") (pin "19") (pinfunction "VDD_19") (pintype "power_in"))
      (node (ref "U2") (pin "3") (pinfunction "SOPWR_3") (pintype "power_in"))
      (node (ref "U3") (pin "1") (pinfunction "VDD_1") (pintype "power_in"))
      (node (ref "U3") (pin "17") (pinfunction "VUSB_17") (pintype "power_in"))
      (node (ref "U4") (pin "5") (pinfunction "VDDIO_5") (pintype "power_in"))
      (node (ref "U4") (pin "8") (pinfunction "VDD_8") (pintype "power_in"))
      (node (ref "U5") (pin "4") (pinfunction "OUTPUT_4") (pintype "output"))
    )
    (net (code "82") (name "unconnected-(X8-Pad4)") (class "Default")
      (node (ref "X8") (pin "4") (pinfunction "4_4") (pintype "passive"))
    )
  )
)
